# FPGAIO.net
KiCad netlist of a schematic drawn in Altium Designer
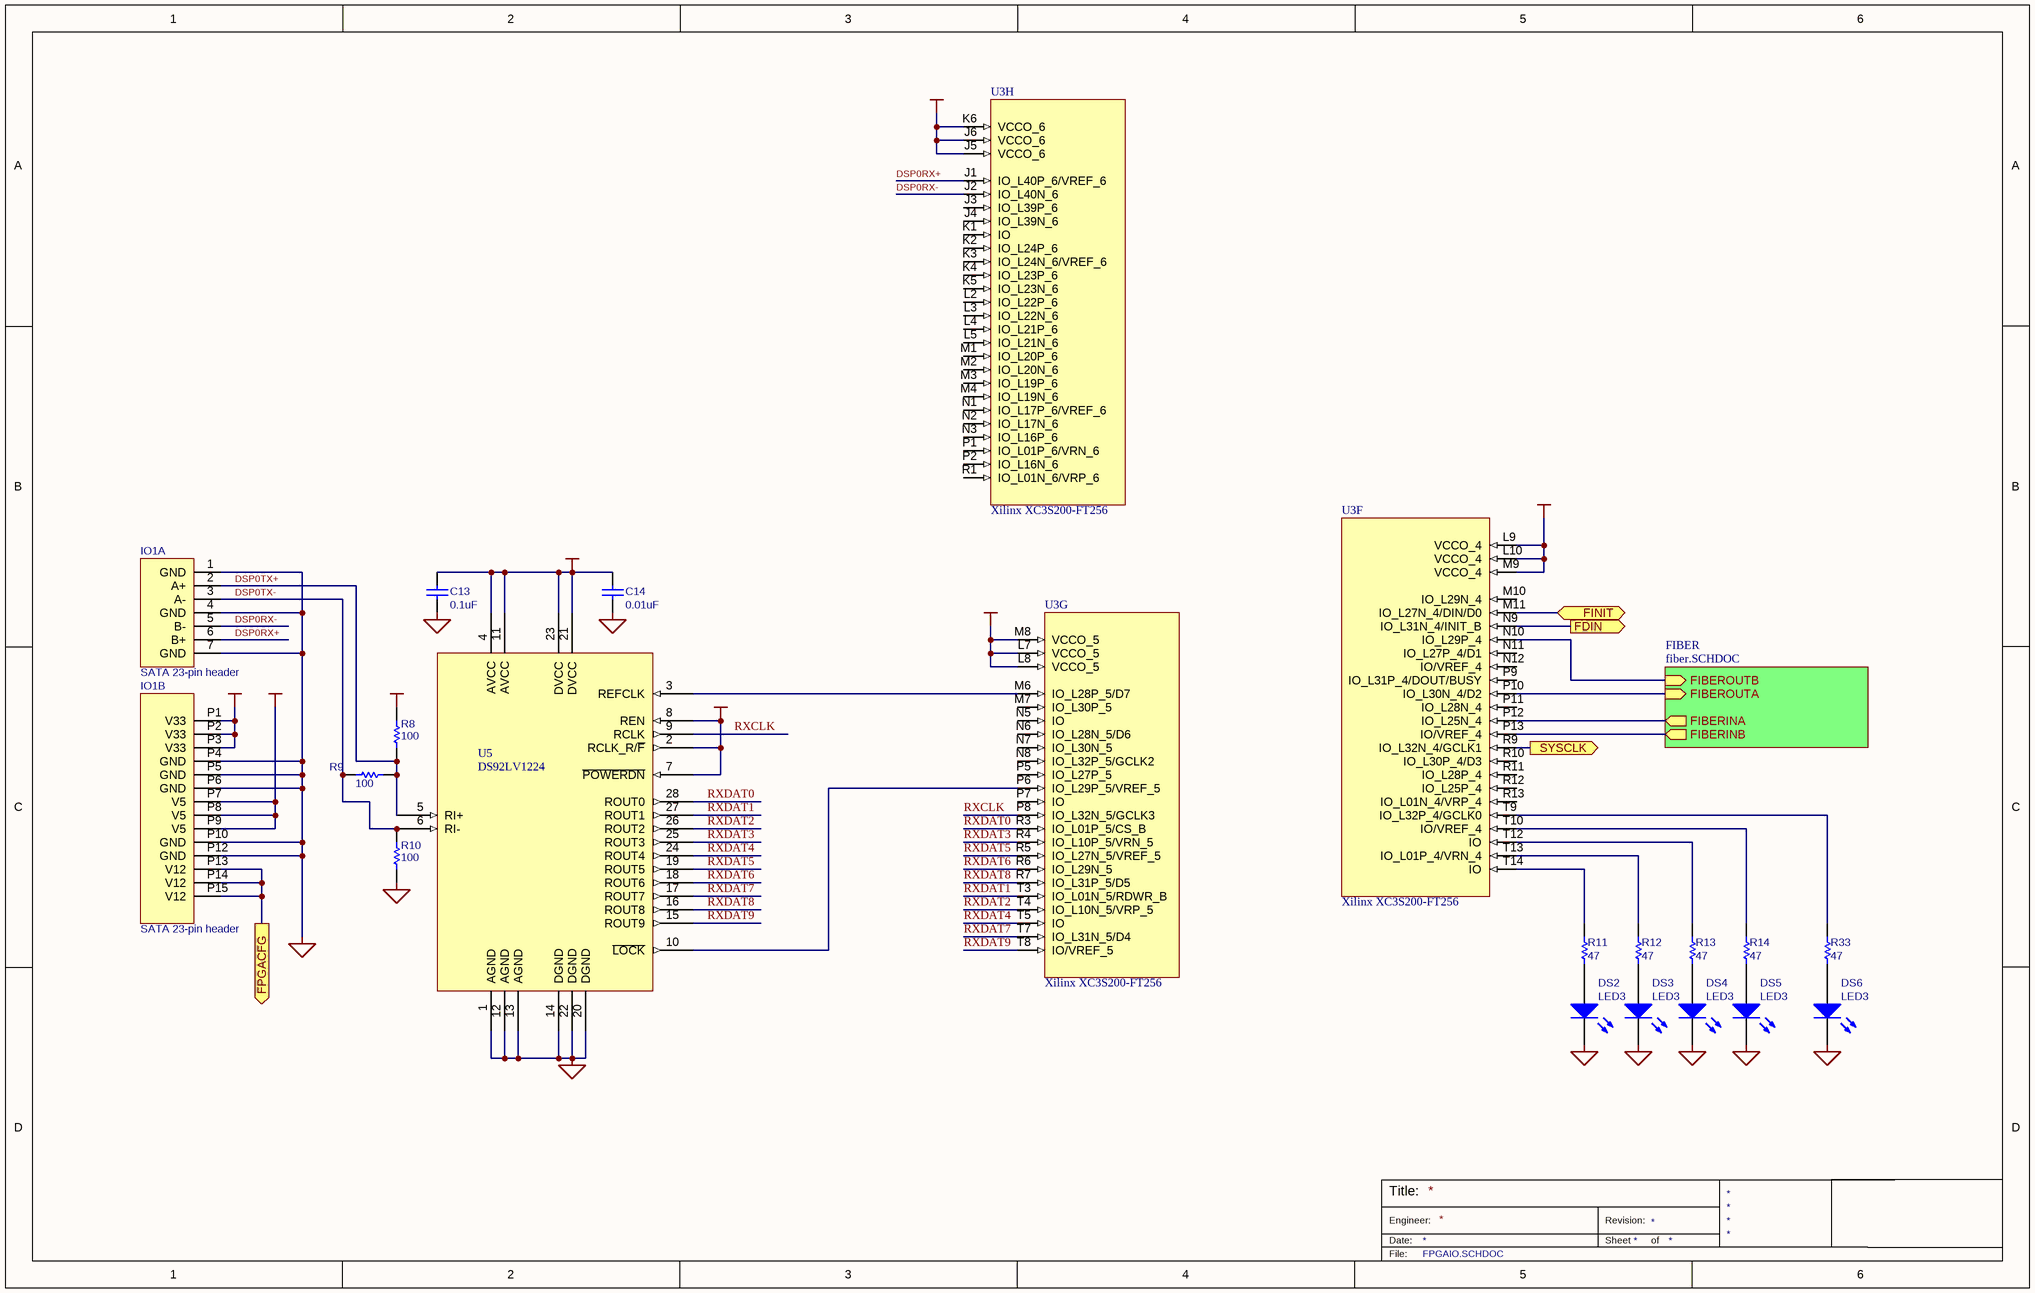
[diagram p0: FPGAIO.SCHDOC]

(export (version "E")
  (design (tool "Eeschema 10.0.6"))
  (components
    (comp (ref "C13")
      (value "0.1uF")
      (footprint "CC1005-0402")
      (description "Capacitor")
      (fields
        (field (name "MANUFACTURER") "Generic Components")
        (field (name "Comment") "Cap")
        (field (name "PUBLISHER") "Altium Limited")
      )
      (libsource (lib "Miscellaneous Devices") (part "Cap"))
    )
    (comp (ref "C14")
      (value "0.01uF")
      (footprint "CC1005-0402")
      (description "Capacitor")
      (fields
        (field (name "MANUFACTURER") "Generic Components")
        (field (name "Comment") "Cap")
        (field (name "PUBLISHER") "Altium Limited")
      )
      (libsource (lib "Miscellaneous Devices") (part "Cap"))
    )
    (comp (ref "DS2")
      (value "LED3")
      (footprint "SMD _LED")
      (description "Typical BLUE SiC LED")
      (fields (field (name "PUBLISHER") "Altium Limited"))
      (libsource (lib "Miscellaneous Devices") (part "LED3"))
    )
    (comp (ref "DS3")
      (value "LED3")
      (footprint "SMD _LED")
      (description "Typical BLUE SiC LED")
      (fields (field (name "PUBLISHER") "Altium Limited"))
      (libsource (lib "Miscellaneous Devices") (part "LED3"))
    )
    (comp (ref "DS4")
      (value "LED3")
      (footprint "SMD _LED")
      (description "Typical BLUE SiC LED")
      (fields (field (name "PUBLISHER") "Altium Limited"))
      (libsource (lib "Miscellaneous Devices") (part "LED3"))
    )
    (comp (ref "DS5")
      (value "LED3")
      (footprint "SMD _LED")
      (description "Typical BLUE SiC LED")
      (fields (field (name "PUBLISHER") "Altium Limited"))
      (libsource (lib "Miscellaneous Devices") (part "LED3"))
    )
    (comp (ref "DS6")
      (value "LED3")
      (footprint "SMD _LED")
      (description "Typical BLUE SiC LED")
      (fields (field (name "PUBLISHER") "Altium Limited"))
      (libsource (lib "Miscellaneous Devices") (part "LED3"))
    )
    (comp (ref "IO1")
      (value "SATA 23-pin header")
      (footprint "MOLEX 87703-0001")
      (libsource (lib "parts") (part "SATA-23"))
    )
    (comp (ref "R8")
      (value "100")
      (footprint "CR1005-0402")
      (description "Resistor")
      (fields (field (name "MANUFACTURER") "Generic Components") (field (name "PUBLISHER") "Altium Limited"))
      (libsource (lib "Miscellaneous Devices") (part "Res1"))
    )
    (comp (ref "R9")
      (value "100")
      (footprint "CR1005-0402")
      (description "Resistor")
      (fields (field (name "MANUFACTURER") "Generic Components") (field (name "PUBLISHER") "Altium Limited"))
      (libsource (lib "Miscellaneous Devices") (part "Res1"))
    )
    (comp (ref "R10")
      (value "100")
      (footprint "CR1005-0402")
      (description "Resistor")
      (fields (field (name "MANUFACTURER") "Generic Components") (field (name "PUBLISHER") "Altium Limited"))
      (libsource (lib "Miscellaneous Devices") (part "Res1"))
    )
    (comp (ref "R11")
      (value "47")
      (footprint "CR1608-0603")
      (description "Resistor")
      (fields
        (field (name "MANUFACTURER") "Generic Components")
        (field (name "Comment") "Res1")
        (field (name "PUBLISHER") "Altium Limited")
      )
      (libsource (lib "Miscellaneous Devices") (part "Res1"))
    )
    (comp (ref "R12")
      (value "47")
      (footprint "CR1608-0603")
      (description "Resistor")
      (fields
        (field (name "MANUFACTURER") "Generic Components")
        (field (name "Comment") "Res1")
        (field (name "PUBLISHER") "Altium Limited")
      )
      (libsource (lib "Miscellaneous Devices") (part "Res1"))
    )
    (comp (ref "R13")
      (value "47")
      (footprint "CR1608-0603")
      (description "Resistor")
      (fields
        (field (name "MANUFACTURER") "Generic Components")
        (field (name "Comment") "Res1")
        (field (name "PUBLISHER") "Altium Limited")
      )
      (libsource (lib "Miscellaneous Devices") (part "Res1"))
    )
    (comp (ref "R14")
      (value "47")
      (footprint "CR1608-0603")
      (description "Resistor")
      (fields
        (field (name "MANUFACTURER") "Generic Components")
        (field (name "Comment") "Res1")
        (field (name "PUBLISHER") "Altium Limited")
      )
      (libsource (lib "Miscellaneous Devices") (part "Res1"))
    )
    (comp (ref "R33")
      (value "47")
      (footprint "CR1608-0603")
      (description "Resistor")
      (fields
        (field (name "MANUFACTURER") "Generic Components")
        (field (name "Comment") "Res1")
        (field (name "PUBLISHER") "Altium Limited")
      )
      (libsource (lib "Miscellaneous Devices") (part "Res1"))
    )
    (comp (ref "U3")
      (value "Xilinx XC3S200-FT256")
      (footprint "Xilinx FT256 BGA")
      (description "Xilinx Spartan-3 FPGA")
      (libsource (lib "") (part "XC3S200-FT256_1"))
    )
    (comp (ref "U5")
      (value "DS92LV1224")
      (footprint "SSO-G28/E4.3")
      (description "30-66 MHz 10-Bit Bus LVDS Deserializer")
      (libsource (lib "parts") (part "DS92LV1224"))
    )
  )
  (nets
    (net (code "1") (name "+2.5VCC") (class "Default")
      (node (ref "U3") (pin "J5") (pinfunction "VCCO_6_J5") (pintype "input"))
      (node (ref "U3") (pin "J6") (pinfunction "VCCO_6_J6") (pintype "input"))
      (node (ref "U3") (pin "K6") (pinfunction "VCCO_6_K6") (pintype "input"))
    )
    (net (code "2") (name "+5VCC") (class "Default")
      (node (ref "IO1") (pin "P7") (pinfunction "V5_P7") (pintype "passive"))
      (node (ref "IO1") (pin "P8") (pinfunction "V5_P8") (pintype "passive"))
      (node (ref "IO1") (pin "P9") (pinfunction "V5_P9") (pintype "passive"))
    )
    (net (code "3") (name "/DSP0RX+") (class "Default")
      (node (ref "IO1") (pin "6") (pinfunction "B+_6") (pintype "passive"))
      (node (ref "U3") (pin "J1") (pinfunction "IO_L40P_6/VREF_6_J1") (pintype "input"))
    )
    (net (code "4") (name "/DSP0RX-") (class "Default")
      (node (ref "IO1") (pin "5") (pinfunction "B-_5") (pintype "passive"))
      (node (ref "U3") (pin "J2") (pinfunction "IO_L40N_6_J2") (pintype "input"))
    )
    (net (code "5") (name "/DSP0TX+") (class "Default")
      (node (ref "IO1") (pin "2") (pinfunction "A+_2") (pintype "passive"))
      (node (ref "R8") (pin "2") (pinfunction "2_2") (pintype "passive"))
      (node (ref "R9") (pin "2") (pinfunction "2_2") (pintype "passive"))
      (node (ref "U5") (pin "5") (pinfunction "RI+_5") (pintype "input"))
    )
    (net (code "6") (name "/DSP0TX-") (class "Default")
      (node (ref "IO1") (pin "3") (pinfunction "A-_3") (pintype "passive"))
      (node (ref "R10") (pin "2") (pinfunction "2_2") (pintype "passive"))
      (node (ref "R9") (pin "1") (pinfunction "1_1") (pintype "passive"))
      (node (ref "U5") (pin "6") (pinfunction "RI-_6") (pintype "input"))
    )
    (net (code "7") (name "/FDIN") (class "Default")
      (node (ref "U3") (pin "N9") (pinfunction "IO_L31N_4/INIT_B_N9") (pintype "input"))
    )
    (net (code "8") (name "/FIBERINA") (class "Default")
      (node (ref "U3") (pin "P12") (pinfunction "IO_L25N_4_P12") (pintype "input"))
    )
    (net (code "9") (name "/FIBERINB") (class "Default")
      (node (ref "U3") (pin "P13") (pinfunction "IO/VREF_4_P13") (pintype "input"))
    )
    (net (code "10") (name "/FIBEROUTA") (class "Default")
      (node (ref "U3") (pin "P10") (pinfunction "IO_L30N_4/D2_P10") (pintype "input"))
    )
    (net (code "11") (name "/FIBEROUTB") (class "Default")
      (node (ref "U3") (pin "N10") (pinfunction "IO_L29P_4_N10") (pintype "input"))
    )
    (net (code "12") (name "/FINIT") (class "Default")
      (node (ref "U3") (pin "M11") (pinfunction "IO_L27N_4/DIN/D0_M11") (pintype "input"))
    )
    (net (code "13") (name "/FPGACFG") (class "Default")
      (node (ref "IO1") (pin "P13") (pinfunction "V12_P13") (pintype "passive"))
      (node (ref "IO1") (pin "P14") (pinfunction "V12_P14") (pintype "passive"))
      (node (ref "IO1") (pin "P15") (pinfunction "V12_P15") (pintype "passive"))
    )
    (net (code "14") (name "/RXCLK") (class "Default")
      (node (ref "U3") (pin "P8") (pinfunction "IO_L32N_5/GCLK3_P8") (pintype "input"))
      (node (ref "U5") (pin "9") (pinfunction "RCLK_9") (pintype "output"))
    )
    (net (code "15") (name "/RXDAT0") (class "Default")
      (node (ref "U3") (pin "R3") (pinfunction "IO_L01P_5/CS_B_R3") (pintype "input"))
      (node (ref "U5") (pin "28") (pinfunction "ROUT0_28") (pintype "output"))
    )
    (net (code "16") (name "/RXDAT1") (class "Default")
      (node (ref "U3") (pin "T3") (pinfunction "IO_L01N_5/RDWR_B_T3") (pintype "input"))
      (node (ref "U5") (pin "27") (pinfunction "ROUT1_27") (pintype "output"))
    )
    (net (code "17") (name "/RXDAT2") (class "Default")
      (node (ref "U3") (pin "T4") (pinfunction "IO_L10N_5/VRP_5_T4") (pintype "input"))
      (node (ref "U5") (pin "26") (pinfunction "ROUT2_26") (pintype "output"))
    )
    (net (code "18") (name "/RXDAT3") (class "Default")
      (node (ref "U3") (pin "R4") (pinfunction "IO_L10P_5/VRN_5_R4") (pintype "input"))
      (node (ref "U5") (pin "25") (pinfunction "ROUT3_25") (pintype "output"))
    )
    (net (code "19") (name "/RXDAT4") (class "Default")
      (node (ref "U3") (pin "T5") (pinfunction "IO_T5") (pintype "input"))
      (node (ref "U5") (pin "24") (pinfunction "ROUT4_24") (pintype "output"))
    )
    (net (code "20") (name "/RXDAT5") (class "Default")
      (node (ref "U3") (pin "R5") (pinfunction "IO_L27N_5/VREF_5_R5") (pintype "input"))
      (node (ref "U5") (pin "19") (pinfunction "ROUT5_19") (pintype "output"))
    )
    (net (code "21") (name "/RXDAT6") (class "Default")
      (node (ref "U3") (pin "R6") (pinfunction "IO_L29N_5_R6") (pintype "input"))
      (node (ref "U5") (pin "18") (pinfunction "ROUT6_18") (pintype "output"))
    )
    (net (code "22") (name "/RXDAT7") (class "Default")
      (node (ref "U3") (pin "T7") (pinfunction "IO_L31N_5/D4_T7") (pintype "input"))
      (node (ref "U5") (pin "17") (pinfunction "ROUT7_17") (pintype "output"))
    )
    (net (code "23") (name "/RXDAT8") (class "Default")
      (node (ref "U3") (pin "R7") (pinfunction "IO_L31P_5/D5_R7") (pintype "input"))
      (node (ref "U5") (pin "16") (pinfunction "ROUT8_16") (pintype "output"))
    )
    (net (code "24") (name "/RXDAT9") (class "Default")
      (node (ref "U3") (pin "T8") (pinfunction "IO/VREF_5_T8") (pintype "input"))
      (node (ref "U5") (pin "15") (pinfunction "ROUT9_15") (pintype "output"))
    )
    (net (code "25") (name "/SYSCLK") (class "Default")
      (node (ref "U3") (pin "R9") (pinfunction "IO_L32N_4/GCLK1_R9") (pintype "input"))
    )
    (net (code "26") (name "GND") (class "Default")
      (node (ref "C13") (pin "1") (pinfunction "1_1") (pintype "passive"))
      (node (ref "C14") (pin "1") (pinfunction "1_1") (pintype "passive"))
      (node (ref "DS2") (pin "2") (pinfunction "K_2") (pintype "passive"))
      (node (ref "DS3") (pin "2") (pinfunction "K_2") (pintype "passive"))
      (node (ref "DS4") (pin "2") (pinfunction "K_2") (pintype "passive"))
      (node (ref "DS5") (pin "2") (pinfunction "K_2") (pintype "passive"))
      (node (ref "DS6") (pin "2") (pinfunction "K_2") (pintype "passive"))
      (node (ref "IO1") (pin "1") (pinfunction "GND_1") (pintype "passive"))
      (node (ref "IO1") (pin "4") (pinfunction "GND_4") (pintype "passive"))
      (node (ref "IO1") (pin "7") (pinfunction "GND_7") (pintype "passive"))
      (node (ref "IO1") (pin "P10") (pinfunction "GND_P10") (pintype "passive"))
      (node (ref "IO1") (pin "P12") (pinfunction "GND_P12") (pintype "passive"))
      (node (ref "IO1") (pin "P4") (pinfunction "GND_P4") (pintype "passive"))
      (node (ref "IO1") (pin "P5") (pinfunction "GND_P5") (pintype "passive"))
      (node (ref "IO1") (pin "P6") (pinfunction "GND_P6") (pintype "passive"))
      (node (ref "R10") (pin "1") (pinfunction "1_1") (pintype "passive"))
      (node (ref "U5") (pin "1") (pinfunction "AGND_1") (pintype "power_in"))
      (node (ref "U5") (pin "12") (pinfunction "AGND_12") (pintype "power_in"))
      (node (ref "U5") (pin "13") (pinfunction "AGND_13") (pintype "power_in"))
      (node (ref "U5") (pin "14") (pinfunction "DGND_14") (pintype "power_in"))
      (node (ref "U5") (pin "20") (pinfunction "DGND_20") (pintype "power_in"))
      (node (ref "U5") (pin "22") (pinfunction "DGND_22") (pintype "power_in"))
    )
    (net (code "27") (name "Net-(DS2-A)") (class "Default")
      (node (ref "DS2") (pin "1") (pinfunction "A_1") (pintype "passive"))
      (node (ref "R11") (pin "2") (pinfunction "2_2") (pintype "passive"))
    )
    (net (code "28") (name "Net-(DS3-A)") (class "Default")
      (node (ref "DS3") (pin "1") (pinfunction "A_1") (pintype "passive"))
      (node (ref "R12") (pin "2") (pinfunction "2_2") (pintype "passive"))
    )
    (net (code "29") (name "Net-(DS4-A)") (class "Default")
      (node (ref "DS4") (pin "1") (pinfunction "A_1") (pintype "passive"))
      (node (ref "R13") (pin "2") (pinfunction "2_2") (pintype "passive"))
    )
    (net (code "30") (name "Net-(DS5-A)") (class "Default")
      (node (ref "DS5") (pin "1") (pinfunction "A_1") (pintype "passive"))
      (node (ref "R14") (pin "2") (pinfunction "2_2") (pintype "passive"))
    )
    (net (code "31") (name "Net-(DS6-A)") (class "Default")
      (node (ref "DS6") (pin "1") (pinfunction "A_1") (pintype "passive"))
      (node (ref "R33") (pin "2") (pinfunction "2_2") (pintype "passive"))
    )
    (net (code "32") (name "Net-(R11-Pad1)") (class "Default")
      (node (ref "R11") (pin "1") (pinfunction "1_1") (pintype "passive"))
      (node (ref "U3") (pin "T14") (pinfunction "IO_T14") (pintype "input"))
    )
    (net (code "33") (name "Net-(R13-Pad1)") (class "Default")
      (node (ref "R13") (pin "1") (pinfunction "1_1") (pintype "passive"))
      (node (ref "U3") (pin "T12") (pinfunction "IO_T12") (pintype "input"))
    )
    (net (code "34") (name "Net-(R14-Pad1)") (class "Default")
      (node (ref "R14") (pin "1") (pinfunction "1_1") (pintype "passive"))
      (node (ref "U3") (pin "T10") (pinfunction "IO/VREF_4_T10") (pintype "input"))
    )
    (net (code "35") (name "Net-(U3F-IO_L01P_4{slash}VRN_4)") (class "Default")
      (node (ref "R12") (pin "1") (pinfunction "1_1") (pintype "passive"))
      (node (ref "U3") (pin "T13") (pinfunction "IO_L01P_4/VRN_4_T13") (pintype "input"))
    )
    (net (code "36") (name "Net-(U3F-IO_L32P_4{slash}GCLK0)") (class "Default")
      (node (ref "R33") (pin "1") (pinfunction "1_1") (pintype "passive"))
      (node (ref "U3") (pin "T9") (pinfunction "IO_L32P_4/GCLK0_T9") (pintype "input"))
    )
    (net (code "37") (name "Net-(U3G-IO_L28P_5{slash}D7)") (class "Default")
      (node (ref "U3") (pin "M6") (pinfunction "IO_L28P_5/D7_M6") (pintype "input"))
      (node (ref "U5") (pin "3") (pinfunction "REFCLK_3") (pintype "input"))
    )
    (net (code "38") (name "Net-(U3G-IO_L29P_5{slash}VREF_5)") (class "Default")
      (node (ref "U3") (pin "P6") (pinfunction "IO_L29P_5/VREF_5_P6") (pintype "input"))
      (node (ref "U5") (pin "10") (pinfunction "~{LOCK}_10") (pintype "output"))
    )
    (net (code "39") (name "VCC") (class "Default")
      (node (ref "C13") (pin "2") (pinfunction "2_2") (pintype "passive"))
      (node (ref "C14") (pin "2") (pinfunction "2_2") (pintype "passive"))
      (node (ref "IO1") (pin "P1") (pinfunction "V33_P1") (pintype "passive"))
      (node (ref "IO1") (pin "P2") (pinfunction "V33_P2") (pintype "passive"))
      (node (ref "IO1") (pin "P3") (pinfunction "V33_P3") (pintype "passive"))
      (node (ref "R8") (pin "1") (pinfunction "1_1") (pintype "passive"))
      (node (ref "U3") (pin "L10") (pinfunction "VCCO_4_L10") (pintype "input"))
      (node (ref "U3") (pin "L7") (pinfunction "VCCO_5_L7") (pintype "input"))
      (node (ref "U3") (pin "L8") (pinfunction "VCCO_5_L8") (pintype "input"))
      (node (ref "U3") (pin "L9") (pinfunction "VCCO_4_L9") (pintype "input"))
      (node (ref "U3") (pin "M8") (pinfunction "VCCO_5_M8") (pintype "input"))
      (node (ref "U3") (pin "M9") (pinfunction "VCCO_4_M9") (pintype "input"))
      (node (ref "U5") (pin "11") (pinfunction "AVCC_11") (pintype "power_in"))
      (node (ref "U5") (pin "2") (pinfunction "RCLK_R/~{F}_2") (pintype "output"))
      (node (ref "U5") (pin "21") (pinfunction "DVCC_21") (pintype "power_in"))
      (node (ref "U5") (pin "23") (pinfunction "DVCC_23") (pintype "power_in"))
      (node (ref "U5") (pin "4") (pinfunction "AVCC_4") (pintype "power_in"))
      (node (ref "U5") (pin "7") (pinfunction "~{POWERDN}_7") (pintype "input"))
      (node (ref "U5") (pin "8") (pinfunction "REN_8") (pintype "input"))
    )
    (net (code "40") (name "unconnected-(U3F-IO_L01N_4{slash}VRP_4-PadR13)") (class "Default")
      (node (ref "U3") (pin "R13") (pinfunction "IO_L01N_4/VRP_4_R13") (pintype "input"))
    )
    (net (code "41") (name "unconnected-(U3F-IO_L25P_4-PadR12)") (class "Default")
      (node (ref "U3") (pin "R12") (pinfunction "IO_L25P_4_R12") (pintype "input"))
    )
    (net (code "42") (name "unconnected-(U3F-IO_L27P_4{slash}D1-PadN11)") (class "Default")
      (node (ref "U3") (pin "N11") (pinfunction "IO_L27P_4/D1_N11") (pintype "input"))
    )
    (net (code "43") (name "unconnected-(U3F-IO_L28N_4-PadP11)") (class "Default")
      (node (ref "U3") (pin "P11") (pinfunction "IO_L28N_4_P11") (pintype "input"))
    )
    (net (code "44") (name "unconnected-(U3F-IO_L28P_4-PadR11)") (class "Default")
      (node (ref "U3") (pin "R11") (pinfunction "IO_L28P_4_R11") (pintype "input"))
    )
    (net (code "45") (name "unconnected-(U3F-IO_L29N_4-PadM10)") (class "Default")
      (node (ref "U3") (pin "M10") (pinfunction "IO_L29N_4_M10") (pintype "input"))
    )
    (net (code "46") (name "unconnected-(U3F-IO_L30P_4{slash}D3-PadR10)") (class "Default")
      (node (ref "U3") (pin "R10") (pinfunction "IO_L30P_4/D3_R10") (pintype "input"))
    )
    (net (code "47") (name "unconnected-(U3F-IO_L31P_4{slash}DOUT{slash}BUSY-PadP9)") (class "Default")
      (node (ref "U3") (pin "P9") (pinfunction "IO_L31P_4/DOUT/BUSY_P9") (pintype "input"))
    )
    (net (code "48") (name "unconnected-(U3F-IO{slash}VREF_4-PadN12)") (class "Default")
      (node (ref "U3") (pin "N12") (pinfunction "IO/VREF_4_N12") (pintype "input"))
    )
    (net (code "49") (name "unconnected-(U3G-IO-PadN5)") (class "Default")
      (node (ref "U3") (pin "N5") (pinfunction "IO_N5") (pintype "input"))
    )
    (net (code "50") (name "unconnected-(U3G-IO-PadP7)") (class "Default")
      (node (ref "U3") (pin "P7") (pinfunction "IO_P7") (pintype "input"))
    )
    (net (code "51") (name "unconnected-(U3G-IO_L27P_5-PadP5)") (class "Default")
      (node (ref "U3") (pin "P5") (pinfunction "IO_L27P_5_P5") (pintype "input"))
    )
    (net (code "52") (name "unconnected-(U3G-IO_L28N_5{slash}D6-PadN6)") (class "Default")
      (node (ref "U3") (pin "N6") (pinfunction "IO_L28N_5/D6_N6") (pintype "input"))
    )
    (net (code "53") (name "unconnected-(U3G-IO_L30N_5-PadN7)") (class "Default")
      (node (ref "U3") (pin "N7") (pinfunction "IO_L30N_5_N7") (pintype "input"))
    )
    (net (code "54") (name "unconnected-(U3G-IO_L30P_5-PadM7)") (class "Default")
      (node (ref "U3") (pin "M7") (pinfunction "IO_L30P_5_M7") (pintype "input"))
    )
    (net (code "55") (name "unconnected-(U3G-IO_L32P_5{slash}GCLK2-PadN8)") (class "Default")
      (node (ref "U3") (pin "N8") (pinfunction "IO_L32P_5/GCLK2_N8") (pintype "input"))
    )
    (net (code "56") (name "unconnected-(U3H-IO-PadK1)") (class "Default")
      (node (ref "U3") (pin "K1") (pinfunction "IO_K1") (pintype "input"))
    )
    (net (code "57") (name "unconnected-(U3H-IO_L01N_6{slash}VRP_6-PadR1)") (class "Default")
      (node (ref "U3") (pin "R1") (pinfunction "IO_L01N_6/VRP_6_R1") (pintype "input"))
    )
    (net (code "58") (name "unconnected-(U3H-IO_L01P_6{slash}VRN_6-PadP1)") (class "Default")
      (node (ref "U3") (pin "P1") (pinfunction "IO_L01P_6/VRN_6_P1") (pintype "input"))
    )
    (net (code "59") (name "unconnected-(U3H-IO_L16N_6-PadP2)") (class "Default")
      (node (ref "U3") (pin "P2") (pinfunction "IO_L16N_6_P2") (pintype "input"))
    )
    (net (code "60") (name "unconnected-(U3H-IO_L16P_6-PadN3)") (class "Default")
      (node (ref "U3") (pin "N3") (pinfunction "IO_L16P_6_N3") (pintype "input"))
    )
    (net (code "61") (name "unconnected-(U3H-IO_L17N_6-PadN2)") (class "Default")
      (node (ref "U3") (pin "N2") (pinfunction "IO_L17N_6_N2") (pintype "input"))
    )
    (net (code "62") (name "unconnected-(U3H-IO_L17P_6{slash}VREF_6-PadN1)") (class "Default")
      (node (ref "U3") (pin "N1") (pinfunction "IO_L17P_6/VREF_6_N1") (pintype "input"))
    )
    (net (code "63") (name "unconnected-(U3H-IO_L19N_6-PadM4)") (class "Default")
      (node (ref "U3") (pin "M4") (pinfunction "IO_L19N_6_M4") (pintype "input"))
    )
    (net (code "64") (name "unconnected-(U3H-IO_L19P_6-PadM3)") (class "Default")
      (node (ref "U3") (pin "M3") (pinfunction "IO_L19P_6_M3") (pintype "input"))
    )
    (net (code "65") (name "unconnected-(U3H-IO_L20N_6-PadM2)") (class "Default")
      (node (ref "U3") (pin "M2") (pinfunction "IO_L20N_6_M2") (pintype "input"))
    )
    (net (code "66") (name "unconnected-(U3H-IO_L20P_6-PadM1)") (class "Default")
      (node (ref "U3") (pin "M1") (pinfunction "IO_L20P_6_M1") (pintype "input"))
    )
    (net (code "67") (name "unconnected-(U3H-IO_L21N_6-PadL5)") (class "Default")
      (node (ref "U3") (pin "L5") (pinfunction "IO_L21N_6_L5") (pintype "input"))
    )
    (net (code "68") (name "unconnected-(U3H-IO_L21P_6-PadL4)") (class "Default")
      (node (ref "U3") (pin "L4") (pinfunction "IO_L21P_6_L4") (pintype "input"))
    )
    (net (code "69") (name "unconnected-(U3H-IO_L22N_6-PadL3)") (class "Default")
      (node (ref "U3") (pin "L3") (pinfunction "IO_L22N_6_L3") (pintype "input"))
    )
    (net (code "70") (name "unconnected-(U3H-IO_L22P_6-PadL2)") (class "Default")
      (node (ref "U3") (pin "L2") (pinfunction "IO_L22P_6_L2") (pintype "input"))
    )
    (net (code "71") (name "unconnected-(U3H-IO_L23N_6-PadK5)") (class "Default")
      (node (ref "U3") (pin "K5") (pinfunction "IO_L23N_6_K5") (pintype "input"))
    )
    (net (code "72") (name "unconnected-(U3H-IO_L23P_6-PadK4)") (class "Default")
      (node (ref "U3") (pin "K4") (pinfunction "IO_L23P_6_K4") (pintype "input"))
    )
    (net (code "73") (name "unconnected-(U3H-IO_L24N_6{slash}VREF_6-PadK3)") (class "Default")
      (node (ref "U3") (pin "K3") (pinfunction "IO_L24N_6/VREF_6_K3") (pintype "input"))
    )
    (net (code "74") (name "unconnected-(U3H-IO_L24P_6-PadK2)") (class "Default")
      (node (ref "U3") (pin "K2") (pinfunction "IO_L24P_6_K2") (pintype "input"))
    )
    (net (code "75") (name "unconnected-(U3H-IO_L39N_6-PadJ4)") (class "Default")
      (node (ref "U3") (pin "J4") (pinfunction "IO_L39N_6_J4") (pintype "input"))
    )
    (net (code "76") (name "unconnected-(U3H-IO_L39P_6-PadJ3)") (class "Default")
      (node (ref "U3") (pin "J3") (pinfunction "IO_L39P_6_J3") (pintype "input"))
    )
  )
)
